# samDEV_09-rev1_1.net
KiCad netlist of a schematic drawn in EAGLE
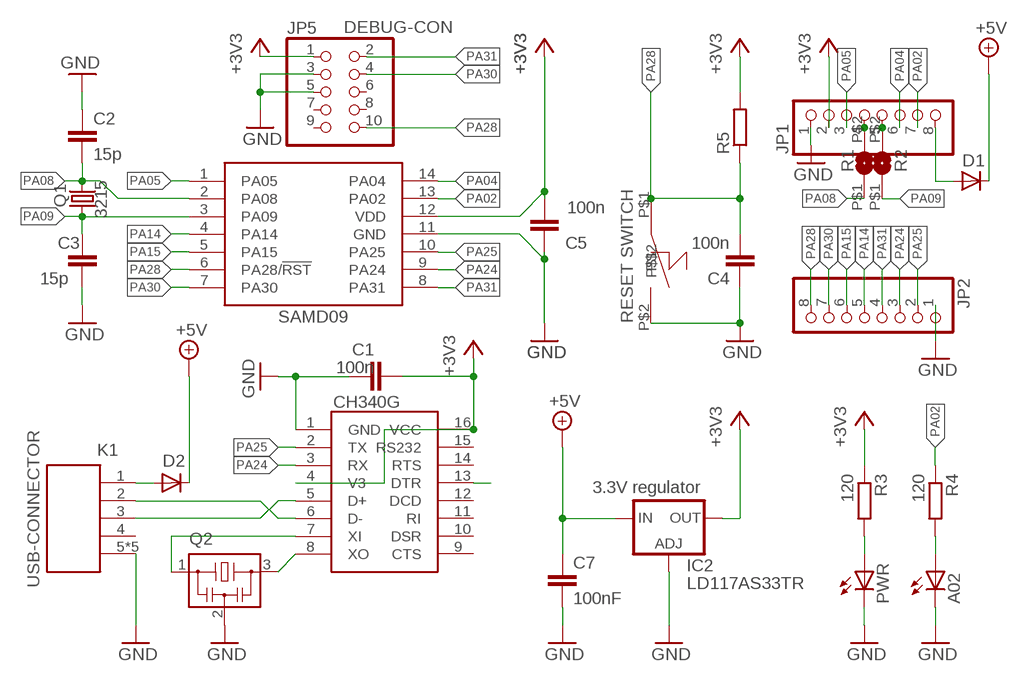
[diagram p0: schematic, sheet 1]

(export (version "E")
  (design (tool "Eeschema 10.0.6"))
  (components
    (comp (ref "A02")
      (value "LEDCHIPLED_0603")
      (footprint "eagle-import:CHIPLED_0603")
      (libsource (lib "eagle-import") (part "LEDCHIPLED_0603"))
    )
    (comp (ref "C1")
      (value "100n")
      (footprint "eagle-import:C0603")
      (libsource (lib "eagle-import") (part "C-EUC0603"))
    )
    (comp (ref "C2")
      (value "15p")
      (footprint "eagle-import:C0603")
      (libsource (lib "eagle-import") (part "C-EUC0603"))
    )
    (comp (ref "C3")
      (value "15p")
      (footprint "eagle-import:C0603")
      (libsource (lib "eagle-import") (part "C-EUC0603"))
    )
    (comp (ref "C4")
      (value "100n")
      (footprint "eagle-import:C0603")
      (libsource (lib "eagle-import") (part "C-EUC0603"))
    )
    (comp (ref "C5")
      (value "100n")
      (footprint "eagle-import:C0603")
      (libsource (lib "eagle-import") (part "C-EUC0603"))
    )
    (comp (ref "C7")
      (value "100nF")
      (footprint "eagle-import:C0603")
      (libsource (lib "eagle-import") (part "C-EUC0603"))
    )
    (comp (ref "D1")
      (value "MBR0520LT")
      (footprint "eagle-import:SOD123")
      (libsource (lib "eagle-import") (part "MBR0520LT"))
    )
    (comp (ref "D2")
      (value "MBR0520LT")
      (footprint "eagle-import:SOD123")
      (libsource (lib "eagle-import") (part "MBR0520LT"))
    )
    (comp (ref "IC1")
      (value "CH340G")
      (footprint "eagle-import:SOIC16")
      (libsource (lib "eagle-import") (part "CH340G"))
    )
    (comp (ref "IC2")
      (value "LD117AS33TR")
      (footprint "eagle-import:SOT223")
      (libsource (lib "eagle-import") (part "LD117A?S33TR"))
    )
    (comp (ref "JP1")
      (value "PINHD-1X8OCTA")
      (footprint "eagle-import:1X08_OCTA")
      (libsource (lib "eagle-import") (part "PINHD-1X8OCTA"))
    )
    (comp (ref "JP2")
      (value "PINHD-1X8OCTA")
      (footprint "eagle-import:1X08_OCTA")
      (libsource (lib "eagle-import") (part "PINHD-1X8OCTA"))
    )
    (comp (ref "JP5")
      (value "PINHD-2X51272")
      (footprint "eagle-import:2X05_1,27B")
      (libsource (lib "eagle-import") (part "PINHD-2X51272"))
    )
    (comp (ref "K1")
      (value "629105136821")
      (footprint "eagle-import:629105136821")
      (libsource (lib "eagle-import") (part "629105136821"))
    )
    (comp (ref "PWR")
      (value "LEDCHIPLED_0603")
      (footprint "eagle-import:CHIPLED_0603")
      (libsource (lib "eagle-import") (part "LEDCHIPLED_0603"))
    )
    (comp (ref "Q1")
      (value "3215")
      (footprint "eagle-import:3215")
      (libsource (lib "eagle-import") (part "3215"))
    )
    (comp (ref "Q2")
      (value "CSTCRCSTCE_SMALL_FOOT")
      (footprint "eagle-import:CSTCESMALL")
      (libsource (lib "eagle-import") (part "CSTCRCSTCE_SMALL_FOOT"))
    )
    (comp (ref "R1")
      (value "SJAL")
      (footprint "eagle-import:SMD_AL1")
      (libsource (lib "eagle-import") (part "SJAL"))
    )
    (comp (ref "R2")
      (value "SJAL")
      (footprint "eagle-import:SMD_AL1")
      (libsource (lib "eagle-import") (part "SJAL"))
    )
    (comp (ref "R3")
      (value "120")
      (footprint "eagle-import:R0603")
      (libsource (lib "eagle-import") (part "R-EU_R0603"))
    )
    (comp (ref "R4")
      (value "120")
      (footprint "eagle-import:R0603")
      (libsource (lib "eagle-import") (part "R-EU_R0603"))
    )
    (comp (ref "R5")
      (value "R-EU_R0603")
      (footprint "eagle-import:R0603")
      (libsource (lib "eagle-import") (part "R-EU_R0603"))
    )
    (comp (ref "S2")
      (value "SMD_SWITCH")
      (footprint "eagle-import:SMDSWITCH")
      (libsource (lib "eagle-import") (part "SMD_SWITCH"))
    )
    (comp (ref "U$1")
      (value "SAMD09SOIC14")
      (footprint "eagle-import:SO14")
      (libsource (lib "eagle-import") (part "SAMD09SOIC14"))
    )
  )
  (nets
    (net (code "1") (name "+3V3") (class "Default")
      (node (ref "C1") (pin "2") (pinfunction "2_2") (pintype "passive"))
      (node (ref "C5") (pin "2") (pinfunction "2_2") (pintype "passive"))
      (node (ref "IC1") (pin "16") (pinfunction "VCC_16") (pintype "bidirectional"))
      (node (ref "IC1") (pin "4") (pinfunction "V3_4") (pintype "bidirectional"))
      (node (ref "IC2") (pin "2") (pinfunction "OUT_2") (pintype "passive"))
      (node (ref "IC2") (pin "4") (pinfunction "OUT_4") (pintype "passive"))
      (node (ref "JP1") (pin "2") (pinfunction "2_2") (pintype "passive"))
      (node (ref "JP5") (pin "1") (pinfunction "1_1") (pintype "passive"))
      (node (ref "R3") (pin "1") (pinfunction "1_1") (pintype "passive"))
      (node (ref "R5") (pin "2") (pinfunction "2_2") (pintype "passive"))
      (node (ref "U$1") (pin "12") (pinfunction "VDD_12") (pintype "bidirectional"))
    )
    (net (code "2") (name "+5V") (class "Default")
      (node (ref "C7") (pin "1") (pinfunction "1_1") (pintype "passive"))
      (node (ref "D1") (pin "C") (pinfunction "C_C") (pintype "passive"))
      (node (ref "D2") (pin "C") (pinfunction "C_C") (pintype "passive"))
      (node (ref "IC2") (pin "3") (pinfunction "IN_3") (pintype "input"))
    )
    (net (code "3") (name "GND") (class "Default")
      (node (ref "A02") (pin "C") (pinfunction "C_C") (pintype "passive"))
      (node (ref "C1") (pin "1") (pinfunction "1_1") (pintype "passive"))
      (node (ref "C2") (pin "1") (pinfunction "1_1") (pintype "passive"))
      (node (ref "C3") (pin "2") (pinfunction "2_2") (pintype "passive"))
      (node (ref "C4") (pin "1") (pinfunction "1_1") (pintype "passive"))
      (node (ref "C5") (pin "1") (pinfunction "1_1") (pintype "passive"))
      (node (ref "C7") (pin "2") (pinfunction "2_2") (pintype "passive"))
      (node (ref "IC1") (pin "1") (pinfunction "GND_1") (pintype "bidirectional"))
      (node (ref "IC2") (pin "1") (pinfunction "ADJ_1") (pintype "input"))
      (node (ref "JP1") (pin "1") (pinfunction "1_1") (pintype "passive"))
      (node (ref "JP2") (pin "1") (pinfunction "1_1") (pintype "passive"))
      (node (ref "JP5") (pin "3") (pinfunction "3_3") (pintype "passive"))
      (node (ref "JP5") (pin "5") (pinfunction "5_5") (pintype "passive"))
      (node (ref "K1") (pin "5") (pinfunction "5_5") (pintype "passive"))
      (node (ref "K1") (pin "Z1") (pinfunction "5_Z1") (pintype "passive"))
      (node (ref "K1") (pin "Z2") (pinfunction "5_Z2") (pintype "passive"))
      (node (ref "K1") (pin "Z3") (pinfunction "5_Z3") (pintype "passive"))
      (node (ref "K1") (pin "Z4") (pinfunction "5_Z4") (pintype "passive"))
      (node (ref "PWR") (pin "C") (pinfunction "C_C") (pintype "passive"))
      (node (ref "Q2") (pin "2") (pinfunction "2_2") (pintype "passive"))
      (node (ref "S2") (pin "P$2") (pinfunction "P$2_P$2") (pintype "bidirectional"))
      (node (ref "U$1") (pin "11") (pinfunction "GND_11") (pintype "bidirectional"))
    )
    (net (code "4") (name "Net-(A02-PadA)") (class "Default")
      (node (ref "A02") (pin "A") (pinfunction "A_A") (pintype "passive"))
      (node (ref "R4") (pin "2") (pinfunction "2_2") (pintype "passive"))
    )
    (net (code "5") (name "Net-(D1-PadA)") (class "Default")
      (node (ref "D1") (pin "A") (pinfunction "A_A") (pintype "passive"))
      (node (ref "JP1") (pin "8") (pinfunction "8_8") (pintype "passive"))
    )
    (net (code "6") (name "Net-(D2-PadA)") (class "Default")
      (node (ref "D2") (pin "A") (pinfunction "A_A") (pintype "passive"))
      (node (ref "K1") (pin "1") (pinfunction "1_1") (pintype "passive"))
    )
    (net (code "7") (name "Net-(IC1-D+)") (class "Default")
      (node (ref "IC1") (pin "5") (pinfunction "D+_5") (pintype "bidirectional"))
      (node (ref "K1") (pin "3") (pinfunction "3_3") (pintype "passive"))
    )
    (net (code "8") (name "Net-(IC1-D-)") (class "Default")
      (node (ref "IC1") (pin "6") (pinfunction "D-_6") (pintype "bidirectional"))
      (node (ref "K1") (pin "2") (pinfunction "2_2") (pintype "passive"))
    )
    (net (code "9") (name "Net-(IC1-XI)") (class "Default")
      (node (ref "IC1") (pin "7") (pinfunction "XI_7") (pintype "bidirectional"))
      (node (ref "Q2") (pin "1") (pinfunction "1_1") (pintype "passive"))
    )
    (net (code "10") (name "Net-(IC1-XO)") (class "Default")
      (node (ref "IC1") (pin "8") (pinfunction "XO_8") (pintype "bidirectional"))
      (node (ref "Q2") (pin "3") (pinfunction "3_3") (pintype "passive"))
    )
    (net (code "11") (name "Net-(PWR-PadA)") (class "Default")
      (node (ref "PWR") (pin "A") (pinfunction "A_A") (pintype "passive"))
      (node (ref "R3") (pin "2") (pinfunction "2_2") (pintype "passive"))
    )
    (net (code "12") (name "Net-(R1-2)") (class "Default")
      (node (ref "JP1") (pin "4") (pinfunction "4_4") (pintype "passive"))
      (node (ref "R1") (pin "P$2") (pinfunction "2_P$2") (pintype "passive"))
    )
    (net (code "13") (name "Net-(R2-2)") (class "Default")
      (node (ref "JP1") (pin "5") (pinfunction "5_5") (pintype "passive"))
      (node (ref "R2") (pin "P$2") (pinfunction "2_P$2") (pintype "passive"))
    )
    (net (code "14") (name "PA02") (class "Default")
      (node (ref "JP1") (pin "7") (pinfunction "7_7") (pintype "passive"))
      (node (ref "R4") (pin "1") (pinfunction "1_1") (pintype "passive"))
      (node (ref "U$1") (pin "13") (pinfunction "PA02_13") (pintype "bidirectional"))
    )
    (net (code "15") (name "PA04") (class "Default")
      (node (ref "JP1") (pin "6") (pinfunction "6_6") (pintype "passive"))
      (node (ref "U$1") (pin "14") (pinfunction "PA04_14") (pintype "bidirectional"))
    )
    (net (code "16") (name "PA05") (class "Default")
      (node (ref "JP1") (pin "3") (pinfunction "3_3") (pintype "passive"))
      (node (ref "U$1") (pin "1") (pinfunction "PA05_1") (pintype "bidirectional"))
    )
    (net (code "17") (name "PA08") (class "Default")
      (node (ref "C2") (pin "2") (pinfunction "2_2") (pintype "passive"))
      (node (ref "Q1") (pin "2") (pinfunction "2_2") (pintype "passive"))
      (node (ref "R1") (pin "P$1") (pinfunction "1_P$1") (pintype "passive"))
      (node (ref "U$1") (pin "2") (pinfunction "PA08_2") (pintype "bidirectional"))
    )
    (net (code "18") (name "PA09") (class "Default")
      (node (ref "C3") (pin "1") (pinfunction "1_1") (pintype "passive"))
      (node (ref "Q1") (pin "1") (pinfunction "1_1") (pintype "passive"))
      (node (ref "R2") (pin "P$1") (pinfunction "1_P$1") (pintype "passive"))
      (node (ref "U$1") (pin "3") (pinfunction "PA09_3") (pintype "bidirectional"))
    )
    (net (code "19") (name "PA14") (class "Default")
      (node (ref "JP2") (pin "5") (pinfunction "5_5") (pintype "passive"))
      (node (ref "U$1") (pin "4") (pinfunction "PA14_4") (pintype "bidirectional"))
    )
    (net (code "20") (name "PA15") (class "Default")
      (node (ref "IC1") (pin "13") (pinfunction "DTR_13") (pintype "bidirectional"))
      (node (ref "JP2") (pin "6") (pinfunction "6_6") (pintype "passive"))
      (node (ref "U$1") (pin "5") (pinfunction "PA15_5") (pintype "bidirectional"))
    )
    (net (code "21") (name "PA24") (class "Default")
      (node (ref "IC1") (pin "3") (pinfunction "RX_3") (pintype "bidirectional"))
      (node (ref "JP2") (pin "3") (pinfunction "3_3") (pintype "passive"))
      (node (ref "U$1") (pin "9") (pinfunction "PA24_9") (pintype "bidirectional"))
    )
    (net (code "22") (name "PA25") (class "Default")
      (node (ref "IC1") (pin "2") (pinfunction "TX_2") (pintype "bidirectional"))
      (node (ref "JP2") (pin "2") (pinfunction "2_2") (pintype "passive"))
      (node (ref "U$1") (pin "10") (pinfunction "PA25_10") (pintype "bidirectional"))
    )
    (net (code "23") (name "PA28") (class "Default")
      (node (ref "C4") (pin "2") (pinfunction "2_2") (pintype "passive"))
      (node (ref "JP2") (pin "8") (pinfunction "8_8") (pintype "passive"))
      (node (ref "JP5") (pin "10") (pinfunction "10_10") (pintype "passive"))
      (node (ref "R5") (pin "1") (pinfunction "1_1") (pintype "passive"))
      (node (ref "S2") (pin "P$1") (pinfunction "P$1_P$1") (pintype "bidirectional"))
      (node (ref "U$1") (pin "6") (pinfunction "PA28/~{RST}_6") (pintype "bidirectional"))
    )
    (net (code "24") (name "PA30") (class "Default")
      (node (ref "JP2") (pin "7") (pinfunction "7_7") (pintype "passive"))
      (node (ref "JP5") (pin "4") (pinfunction "4_4") (pintype "passive"))
      (node (ref "U$1") (pin "7") (pinfunction "PA30_7") (pintype "bidirectional"))
    )
    (net (code "25") (name "PA31") (class "Default")
      (node (ref "JP2") (pin "4") (pinfunction "4_4") (pintype "passive"))
      (node (ref "JP5") (pin "2") (pinfunction "2_2") (pintype "passive"))
      (node (ref "U$1") (pin "8") (pinfunction "PA31_8") (pintype "bidirectional"))
    )
    (net (code "26") (name "unconnected-(IC1-CTS-Pad9)") (class "Default")
      (node (ref "IC1") (pin "9") (pinfunction "CTS_9") (pintype "bidirectional"))
    )
    (net (code "27") (name "unconnected-(IC1-DCD-Pad12)") (class "Default")
      (node (ref "IC1") (pin "12") (pinfunction "DCD_12") (pintype "bidirectional"))
    )
    (net (code "28") (name "unconnected-(IC1-DSR-Pad10)") (class "Default")
      (node (ref "IC1") (pin "10") (pinfunction "DSR_10") (pintype "bidirectional"))
    )
    (net (code "29") (name "unconnected-(IC1-RI-Pad11)") (class "Default")
      (node (ref "IC1") (pin "11") (pinfunction "RI_11") (pintype "bidirectional"))
    )
    (net (code "30") (name "unconnected-(IC1-RS232-Pad15)") (class "Default")
      (node (ref "IC1") (pin "15") (pinfunction "RS232_15") (pintype "bidirectional"))
    )
    (net (code "31") (name "unconnected-(IC1-RTS-Pad14)") (class "Default")
      (node (ref "IC1") (pin "14") (pinfunction "RTS_14") (pintype "bidirectional"))
    )
    (net (code "32") (name "unconnected-(JP5-Pad6)") (class "Default")
      (node (ref "JP5") (pin "6") (pinfunction "6_6") (pintype "passive"))
    )
    (net (code "33") (name "unconnected-(JP5-Pad7)") (class "Default")
      (node (ref "JP5") (pin "7") (pinfunction "7_7") (pintype "passive"))
    )
    (net (code "34") (name "unconnected-(JP5-Pad8)") (class "Default")
      (node (ref "JP5") (pin "8") (pinfunction "8_8") (pintype "passive"))
    )
    (net (code "35") (name "unconnected-(JP5-Pad9)") (class "Default")
      (node (ref "JP5") (pin "9") (pinfunction "9_9") (pintype "passive"))
    )
    (net (code "36") (name "unconnected-(K1-Pad4)") (class "Default")
      (node (ref "K1") (pin "4") (pinfunction "4_4") (pintype "passive"))
    )
  )
)
